# 04_POWER.net
KiCad netlist of a schematic drawn in Altium Designer
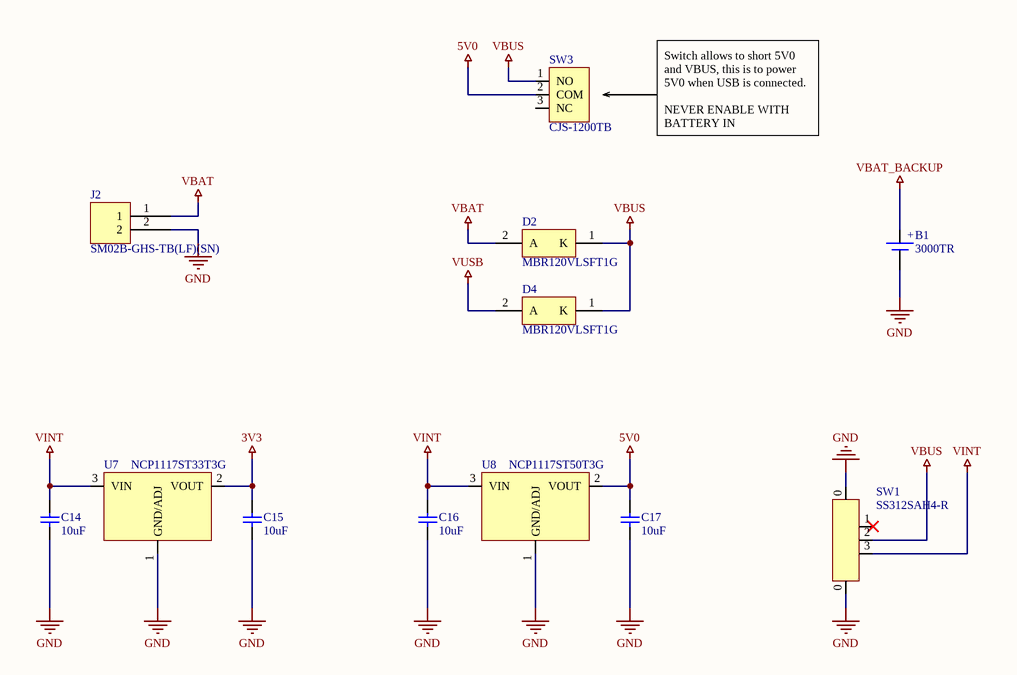
[diagram p0: [04] POWER.SchDoc]

(export (version "E")
  (design (tool "Eeschema 10.0.6"))
  (components
    (comp (ref "B1")
      (value "3000TR")
      (footprint "3000TR")
      (description "HOLDER BATTERY COIN 12MM DIA SMD")
      (fields (field (name "MANUFACTURER") "Keystone Electronics"))
      (libsource (lib "Connectors - Batteries") (part "3000TR"))
    )
    (comp (ref "C14")
      (value "10uF")
      (footprint "INCH 0805 - METRIC 2012 - H140")
      (description "CAP CER 10UF 25V X5R 0805")
      (fields
        (field (name "MANUFACTURER") "Murata")
        (field (name "MANUFACTURER PART NUMBER") "GRM21BR61E106MA73L")
      )
      (libsource (lib "Capacitors") (part "GRM21BR61E106MA73L"))
    )
    (comp (ref "C15")
      (value "10uF")
      (footprint "INCH 0805 - METRIC 2012 - H140")
      (description "CAP CER 10UF 25V X5R 0805")
      (fields
        (field (name "MANUFACTURER") "Murata")
        (field (name "MANUFACTURER PART NUMBER") "GRM21BR61E106MA73L")
      )
      (libsource (lib "Capacitors") (part "GRM21BR61E106MA73L"))
    )
    (comp (ref "C16")
      (value "10uF")
      (footprint "INCH 0805 - METRIC 2012 - H140")
      (description "CAP CER 10UF 25V X5R 0805")
      (fields
        (field (name "MANUFACTURER") "Murata")
        (field (name "MANUFACTURER PART NUMBER") "GRM21BR61E106MA73L")
      )
      (libsource (lib "Capacitors") (part "GRM21BR61E106MA73L"))
    )
    (comp (ref "C17")
      (value "10uF")
      (footprint "INCH 0805 - METRIC 2012 - H140")
      (description "CAP CER 10UF 25V X5R 0805")
      (fields
        (field (name "MANUFACTURER") "Murata")
        (field (name "MANUFACTURER PART NUMBER") "GRM21BR61E106MA73L")
      )
      (libsource (lib "Capacitors") (part "GRM21BR61E106MA73L"))
    )
    (comp (ref "D2")
      (value "MBR120VLSFT1G")
      (footprint "ONSC-SOD-123FL-2-498-01_V")
      (description "Schottky Power Rectifier, 2-Pin SOD-123, Pb-Free, Tape and Reel")
      (fields (field (name "MANUFACTURER") "On Semiconductor"))
      (libsource (lib "Altium Content Vault") (part "ONSC-D-K1A2-2_A"))
    )
    (comp (ref "D4")
      (value "MBR120VLSFT1G")
      (footprint "ONSC-SOD-123FL-2-498-01_V")
      (description "Schottky Power Rectifier, 2-Pin SOD-123, Pb-Free, Tape and Reel")
      (fields (field (name "MANUFACTURER") "On Semiconductor"))
      (libsource (lib "Altium Content Vault") (part "ONSC-D-K1A2-2_A"))
    )
    (comp (ref "J2")
      (value "SM02B-GHS-TB(LF)(SN)")
      (footprint "SM02B-GHS-TB(LF)(SN)")
      (fields (field (name "MANUFACTURER") "JST"))
      (libsource (lib "Connectors") (part "SM02B-GHS-TB(LF)(SN)"))
    )
    (comp (ref "SW1")
      (value "SS312SAH4-R")
      (footprint "NKK_SS312SAH4")
      (description "SWITCH SLIDE SPDT 0.4VA 28V")
      (fields (field (name "MANUFACTURER") "NKK Switches"))
      (libsource (lib "Switches") (part "SS312SAH4-R"))
    )
    (comp (ref "SW3")
      (value "CJS-1200TB")
      (footprint "NCE_CJS-1200TB")
      (description "SWITCH SLIDE SPDT 100MA 6V")
      (fields (field (name "MANUFACTURER") "Nidec Copal"))
      (libsource (lib "Switches") (part "CJS-1200TB"))
    )
    (comp (ref "U7")
      (value "NCP1117ST33T3G")
      (footprint "SOT223-4P230_700X180L90X70")
      (description "IC REG LINEAR 3.3V 1A SOT223")
      (fields (field (name "MANUFACTURER") "ON Semiconductor"))
      (libsource (lib "Voltage Regulators - Linear") (part "NCP1117ST33T3G"))
    )
    (comp (ref "U8")
      (value "NCP1117ST50T3G")
      (footprint "SOT223-4P230_700X180L90X70")
      (description "IC REG LINEAR 5V 1A SOT223")
      (fields (field (name "MANUFACTURER") "ON Semiconductor") (field (name "TOLERANCE") "1%"))
      (libsource (lib "Voltage Regulators - Linear") (part "NCP1117ST50T3G"))
    )
  )
  (nets
    (net (code "1") (name "3V3") (class "Default")
      (node (ref "C15") (pin "2") (pintype "passive"))
      (node (ref "U7") (pin "2") (pinfunction "VOUT_2") (pintype "passive"))
    )
    (net (code "2") (name "5V0") (class "Default")
      (node (ref "C17") (pin "2") (pintype "passive"))
      (node (ref "SW3") (pin "2") (pinfunction "COM_2") (pintype "passive"))
      (node (ref "U8") (pin "2") (pinfunction "VOUT_2") (pintype "passive"))
    )
    (net (code "3") (name "GND") (class "Default")
      (node (ref "B1") (pin "2") (pinfunction "-_2") (pintype "passive"))
      (node (ref "C14") (pin "1") (pintype "passive"))
      (node (ref "C15") (pin "1") (pintype "passive"))
      (node (ref "C16") (pin "1") (pintype "passive"))
      (node (ref "C17") (pin "1") (pintype "passive"))
      (node (ref "J2") (pin "2") (pinfunction "2_2") (pintype "passive"))
      (node (ref "SW1") (pin "0") (pintype "passive"))
      (node (ref "U7") (pin "1") (pinfunction "GND/ADJ_1") (pintype "passive"))
      (node (ref "U8") (pin "1") (pinfunction "GND/ADJ_1") (pintype "passive"))
    )
    (net (code "4") (name "VBAT") (class "Default")
      (node (ref "D2") (pin "2") (pinfunction "A_2") (pintype "passive"))
      (node (ref "J2") (pin "1") (pinfunction "1_1") (pintype "passive"))
    )
    (net (code "5") (name "VBAT_BACKUP") (class "Default")
      (node (ref "B1") (pin "1") (pinfunction "+_1") (pintype "passive"))
    )
    (net (code "6") (name "VBUS") (class "Default")
      (node (ref "D2") (pin "1") (pinfunction "K_1") (pintype "passive"))
      (node (ref "D4") (pin "1") (pinfunction "K_1") (pintype "passive"))
      (node (ref "SW1") (pin "2") (pintype "passive"))
      (node (ref "SW3") (pin "1") (pinfunction "NO_1") (pintype "passive"))
    )
    (net (code "7") (name "VINT") (class "Default")
      (node (ref "C14") (pin "2") (pintype "passive"))
      (node (ref "C16") (pin "2") (pintype "passive"))
      (node (ref "SW1") (pin "3") (pintype "passive"))
      (node (ref "U7") (pin "3") (pinfunction "VIN_3") (pintype "passive"))
      (node (ref "U8") (pin "3") (pinfunction "VIN_3") (pintype "passive"))
    )
    (net (code "8") (name "VUSB") (class "Default")
      (node (ref "D4") (pin "2") (pinfunction "A_2") (pintype "passive"))
    )
    (net (code "9") (name "unconnected-(SW1-Pad1)") (class "Default")
      (node (ref "SW1") (pin "1") (pintype "passive+no_connect"))
    )
    (net (code "10") (name "unconnected-(SW3-NC-Pad3)") (class "Default")
      (node (ref "SW3") (pin "3") (pinfunction "NC_3") (pintype "passive"))
    )
  )
)
